# design.net
KiCad netlist of a schematic drawn in Altium Designer
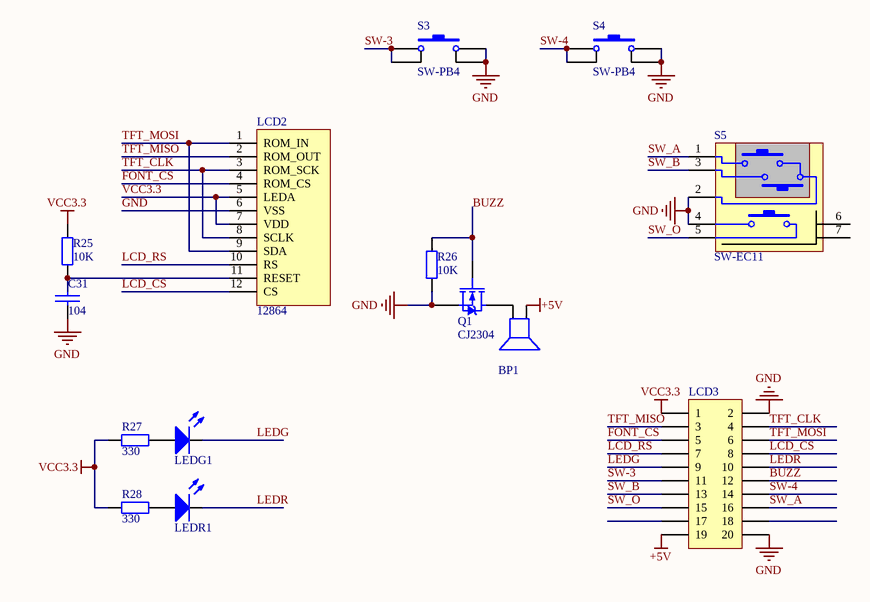
[diagram p0: 显示面板.SchDoc]

(export (version "E")
  (design (tool "Eeschema 10.0.6"))
  (components
    (comp (ref "BP1")
      (value "BUZZER")
      (footprint "蜂鸣器")
      (description "蜂鸣器")
      (libsource (lib "MY_Library") (part "BUZZER"))
    )
    (comp (ref "C31")
      (value "104")
      (footprint "0603C")
      (description "安规电容")
      (libsource (lib "MY_Library") (part "CAP X"))
    )
    (comp (ref "LCD2")
      (value "12864")
      (footprint "LCD12864-1.7inch")
      (description "1.7寸SPI12864屏")
      (libsource (lib "Fszhang") (part "LCD12864串口屏"))
    )
    (comp (ref "LCD3")
      (value "LCD")
      (footprint "HDR10X2_A1")
      (description "Header, 10-Pin")
      (fields (field (name "PUBLISHER") "Altium Limited"))
      (libsource (lib "Fszhang") (part "Header 10X2"))
    )
    (comp (ref "LEDG1") (value "COLOUR") (footprint "LEDφ6") (libsource (lib "MY_Library") (part "ledφ6")))
    (comp (ref "LEDR1") (value "COLOUR") (footprint "LEDφ6") (libsource (lib "MY_Library") (part "ledφ6")))
    (comp (ref "Q1")
      (value "CJ2304")
      (footprint "SOT-23")
      (description "N-Channel MOSFET")
      (fields (field (name "PUBLISHER") "Altium Limited"))
      (libsource (lib "Fszhang") (part "MOSFET-N"))
    )
    (comp (ref "R25")
      (value "10K")
      (footprint "0603-1")
      (description "贴片电阻")
      (fields (field (name "Comment") "Res1") (field (name "PUBLISHER") "Altium Limited"))
      (libsource (lib "") (part "Res1_1"))
    )
    (comp (ref "R26")
      (value "10K")
      (footprint "0603-1")
      (description "贴片电阻")
      (fields (field (name "Comment") "Res1") (field (name "PUBLISHER") "Altium Limited"))
      (libsource (lib "") (part "Res1_1"))
    )
    (comp (ref "R27")
      (value "330")
      (footprint "0603-1")
      (description "贴片电阻")
      (fields (field (name "Comment") "Res1") (field (name "PUBLISHER") "Altium Limited"))
      (libsource (lib "Fszhang") (part "Res1"))
    )
    (comp (ref "R28")
      (value "330")
      (footprint "0603-1")
      (description "贴片电阻")
      (fields (field (name "Comment") "Res1") (field (name "PUBLISHER") "Altium Limited"))
      (libsource (lib "Fszhang") (part "Res1"))
    )
    (comp (ref "S3")
      (value "SW-PB4")
      (footprint "SW_PB4_A1")
      (description "微动开关")
      (fields (field (name "PUBLISHER") "Altium Limited"))
      (libsource (lib "Fszhang") (part "SW-PB4"))
    )
    (comp (ref "S4")
      (value "SW-PB4")
      (footprint "SW_PB4_A1")
      (description "微动开关")
      (fields (field (name "PUBLISHER") "Altium Limited"))
      (libsource (lib "Fszhang") (part "SW-PB4"))
    )
    (comp (ref "S5")
      (value "SW-EC11")
      (footprint "EC11")
      (description "旋转编码开关")
      (fields (field (name "PUBLISHER") "Altium Limited"))
      (libsource (lib "Fszhang") (part "SW-EC11"))
    )
  )
  (nets
    (net (code "1") (name "+5V") (class "Default")
      (node (ref "BP1") (pin "1") (pinfunction "+_1") (pintype "passive"))
      (node (ref "LCD3") (pin "19") (pinfunction "19_19") (pintype "passive"))
    )
    (net (code "2") (name "/BUZZ") (class "Default")
      (node (ref "LCD3") (pin "12") (pinfunction "12_12") (pintype "passive"))
      (node (ref "Q1") (pin "1") (pinfunction "G_1") (pintype "passive"))
      (node (ref "R26") (pin "2") (pinfunction "2_2") (pintype "passive"))
    )
    (net (code "3") (name "/FONT_CS") (class "Default")
      (node (ref "LCD2") (pin "4") (pinfunction "ROM_CS_4") (pintype "passive"))
      (node (ref "LCD3") (pin "5") (pinfunction "5_5") (pintype "passive"))
    )
    (net (code "4") (name "/LCD_CS") (class "Default")
      (node (ref "LCD2") (pin "12") (pinfunction "CS_12") (pintype "passive"))
      (node (ref "LCD3") (pin "8") (pinfunction "8_8") (pintype "passive"))
    )
    (net (code "5") (name "/LCD_RS") (class "Default")
      (node (ref "LCD2") (pin "10") (pinfunction "RS_10") (pintype "passive"))
      (node (ref "LCD3") (pin "7") (pinfunction "7_7") (pintype "passive"))
    )
    (net (code "6") (name "/LEDG") (class "Default")
      (node (ref "LCD3") (pin "9") (pinfunction "9_9") (pintype "passive"))
      (node (ref "LEDG1") (pin "2") (pinfunction "-_2") (pintype "passive"))
    )
    (net (code "7") (name "/LEDR") (class "Default")
      (node (ref "LCD3") (pin "10") (pinfunction "10_10") (pintype "passive"))
      (node (ref "LEDR1") (pin "2") (pinfunction "-_2") (pintype "passive"))
    )
    (net (code "8") (name "/SW-3") (class "Default")
      (node (ref "LCD3") (pin "11") (pinfunction "11_11") (pintype "passive"))
      (node (ref "S3") (pin "1") (pinfunction "1_1") (pintype "passive"))
      (node (ref "S3") (pin "4") (pinfunction "4_4") (pintype "passive"))
    )
    (net (code "9") (name "/SW-4") (class "Default")
      (node (ref "LCD3") (pin "14") (pinfunction "14_14") (pintype "passive"))
      (node (ref "S4") (pin "1") (pinfunction "1_1") (pintype "passive"))
      (node (ref "S4") (pin "4") (pinfunction "4_4") (pintype "passive"))
    )
    (net (code "10") (name "/SW_A") (class "Default")
      (node (ref "LCD3") (pin "16") (pinfunction "16_16") (pintype "passive"))
      (node (ref "S5") (pin "1") (pinfunction "1_1") (pintype "passive"))
    )
    (net (code "11") (name "/SW_B") (class "Default")
      (node (ref "LCD3") (pin "13") (pinfunction "13_13") (pintype "passive"))
      (node (ref "S5") (pin "3") (pinfunction "3_3") (pintype "passive"))
    )
    (net (code "12") (name "/SW_O") (class "Default")
      (node (ref "LCD3") (pin "15") (pinfunction "15_15") (pintype "passive"))
      (node (ref "S5") (pin "5") (pinfunction "5_5") (pintype "passive"))
    )
    (net (code "13") (name "/TFT_CLK") (class "Default")
      (node (ref "LCD2") (pin "3") (pinfunction "ROM_SCK_3") (pintype "passive"))
      (node (ref "LCD2") (pin "8") (pinfunction "SCLK_8") (pintype "passive"))
      (node (ref "LCD3") (pin "4") (pinfunction "4_4") (pintype "passive"))
    )
    (net (code "14") (name "/TFT_MISO") (class "Default")
      (node (ref "LCD2") (pin "2") (pinfunction "ROM_OUT_2") (pintype "passive"))
      (node (ref "LCD3") (pin "3") (pinfunction "3_3") (pintype "passive"))
    )
    (net (code "15") (name "/TFT_MOSI") (class "Default")
      (node (ref "LCD2") (pin "1") (pinfunction "ROM_IN_1") (pintype "passive"))
      (node (ref "LCD2") (pin "9") (pinfunction "SDA_9") (pintype "passive"))
      (node (ref "LCD3") (pin "6") (pinfunction "6_6") (pintype "passive"))
    )
    (net (code "16") (name "GND") (class "Default")
      (node (ref "C31") (pin "1") (pinfunction "1_1") (pintype "passive"))
      (node (ref "LCD2") (pin "6") (pinfunction "VSS_6") (pintype "passive"))
      (node (ref "LCD3") (pin "2") (pinfunction "2_2") (pintype "passive"))
      (node (ref "LCD3") (pin "20") (pinfunction "20_20") (pintype "passive"))
      (node (ref "Q1") (pin "2") (pinfunction "S_2") (pintype "passive"))
      (node (ref "R26") (pin "1") (pinfunction "1_1") (pintype "passive"))
      (node (ref "S3") (pin "2") (pinfunction "2_2") (pintype "passive"))
      (node (ref "S3") (pin "3") (pinfunction "3_3") (pintype "passive"))
      (node (ref "S4") (pin "2") (pinfunction "2_2") (pintype "passive"))
      (node (ref "S4") (pin "3") (pinfunction "3_3") (pintype "passive"))
      (node (ref "S5") (pin "2") (pinfunction "2_2") (pintype "passive"))
      (node (ref "S5") (pin "4") (pinfunction "4_4") (pintype "passive"))
    )
    (net (code "17") (name "Net-(BP1--)") (class "Default")
      (node (ref "BP1") (pin "2") (pinfunction "-_2") (pintype "passive"))
      (node (ref "Q1") (pin "3") (pinfunction "D_3") (pintype "passive"))
    )
    (net (code "18") (name "Net-(LCD2-RESET)") (class "Default")
      (node (ref "C31") (pin "2") (pinfunction "2_2") (pintype "passive"))
      (node (ref "LCD2") (pin "11") (pinfunction "RESET_11") (pintype "passive"))
      (node (ref "R25") (pin "1") (pinfunction "1_1") (pintype "passive"))
    )
    (net (code "19") (name "Net-(LEDG1-+)") (class "Default")
      (node (ref "LEDG1") (pin "1") (pinfunction "+_1") (pintype "passive"))
      (node (ref "R27") (pin "1") (pinfunction "1_1") (pintype "passive"))
    )
    (net (code "20") (name "Net-(LEDR1-+)") (class "Default")
      (node (ref "LEDR1") (pin "1") (pinfunction "+_1") (pintype "passive"))
      (node (ref "R28") (pin "1") (pinfunction "1_1") (pintype "passive"))
    )
    (net (code "21") (name "VCC3.3") (class "Default")
      (node (ref "LCD2") (pin "5") (pinfunction "LEDA_5") (pintype "passive"))
      (node (ref "LCD2") (pin "7") (pinfunction "VDD_7") (pintype "passive"))
      (node (ref "LCD3") (pin "1") (pinfunction "1_1") (pintype "passive"))
      (node (ref "R25") (pin "2") (pinfunction "2_2") (pintype "passive"))
      (node (ref "R27") (pin "2") (pinfunction "2_2") (pintype "passive"))
      (node (ref "R28") (pin "2") (pinfunction "2_2") (pintype "passive"))
    )
    (net (code "22") (name "unconnected-(LCD3-Pad17)") (class "Default")
      (node (ref "LCD3") (pin "17") (pinfunction "17_17") (pintype "passive"))
    )
    (net (code "23") (name "unconnected-(LCD3-Pad18)") (class "Default")
      (node (ref "LCD3") (pin "18") (pinfunction "18_18") (pintype "passive"))
    )
    (net (code "24") (name "unconnected-(S5-Pad6)") (class "Default")
      (node (ref "S5") (pin "6") (pinfunction "6_6") (pintype "passive"))
    )
    (net (code "25") (name "unconnected-(S5-Pad7)") (class "Default")
      (node (ref "S5") (pin "7") (pinfunction "7_7") (pintype "passive"))
    )
  )
)
